# 0x2B.net
KiCad netlist of a schematic drawn in EasyEDA Pro
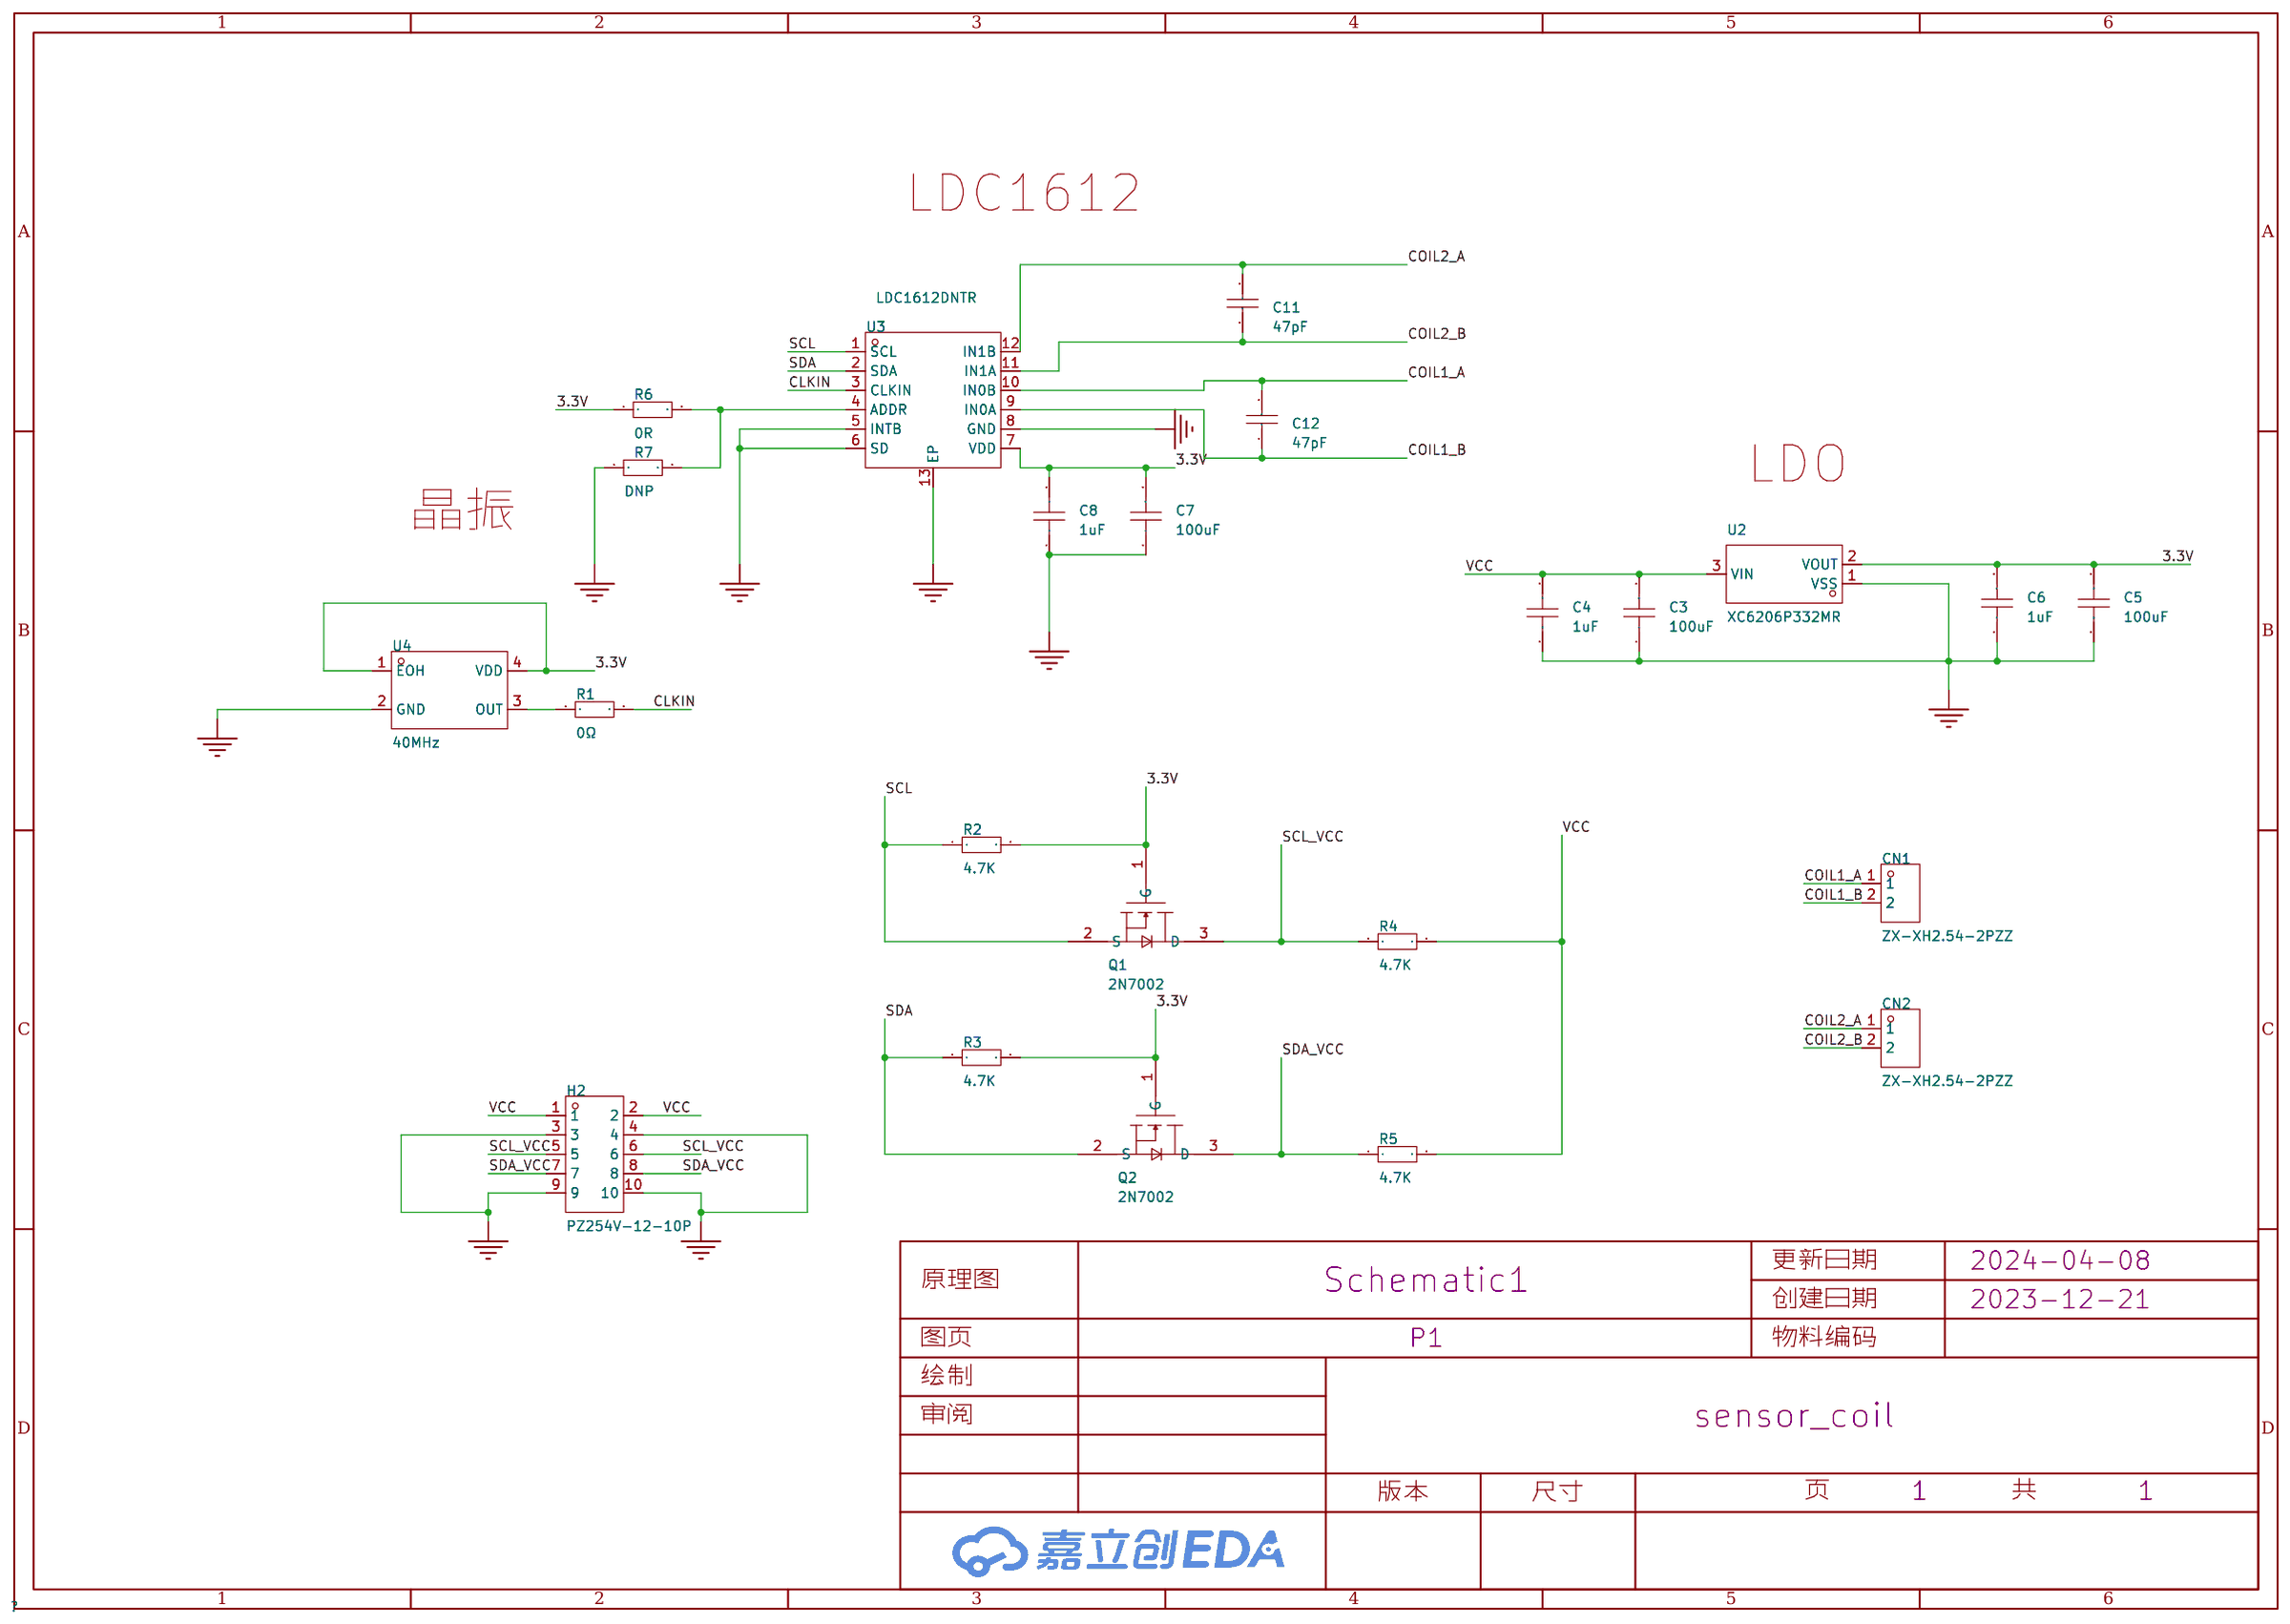
[diagram p0: schematic sheet]

(export (version "E")
  (design (tool "Eeschema 10.0.6"))
  (components
    (comp (ref "C3")
      (value "100uF")
      (footprint "easyedapro:C0603")
      (libsource (lib "easyedapro") (part "CapAcitance"))
    )
    (comp (ref "C4")
      (value "1uF")
      (footprint "easyedapro:C0603")
      (libsource (lib "easyedapro") (part "CapAcitance"))
    )
    (comp (ref "C5")
      (value "100uF")
      (footprint "easyedapro:C0603")
      (libsource (lib "easyedapro") (part "CapAcitance"))
    )
    (comp (ref "C6")
      (value "1uF")
      (footprint "easyedapro:C0603")
      (libsource (lib "easyedapro") (part "CapAcitance"))
    )
    (comp (ref "C7")
      (value "100uF")
      (footprint "easyedapro:C0603")
      (libsource (lib "easyedapro") (part "CapAcitance"))
    )
    (comp (ref "C8")
      (value "1uF")
      (footprint "easyedapro:C0603")
      (libsource (lib "easyedapro") (part "CapAcitance"))
    )
    (comp (ref "C11")
      (value "47pF")
      (footprint "easyedapro:C0402")
      (description "容值:47pF;精度:±5%;额定电压:50V;材质(温度系数):C0G;")
      (fields (field (name "Manufacturer Part") "0402CG470J500NT") (field (name "Manufacturer") "FH(风华)"))
      (libsource (lib "easyedapro") (part "0402CG470J500NT"))
    )
    (comp (ref "C12")
      (value "47pF")
      (footprint "easyedapro:C0402")
      (description "容值:47pF;精度:±5%;额定电压:50V;材质(温度系数):C0G;")
      (fields (field (name "Manufacturer Part") "0402CG470J500NT") (field (name "Manufacturer") "FH(风华)"))
      (libsource (lib "easyedapro") (part "0402CG470J500NT"))
    )
    (comp (ref "CN1")
      (value "ZX-XH2.54-2PZZ")
      (footprint "easyedapro:CONN-TH_2P-P2.50_HX25003-2A")
      (fields (field (name "Manufacturer") "Megastar(兆星)"))
      (libsource (lib "easyedapro") (part "ZX-XH2.54-2PZZ"))
    )
    (comp (ref "CN2")
      (value "ZX-XH2.54-2PZZ")
      (footprint "easyedapro:CONN-TH_2P-P2.50_HX25003-2A")
      (fields (field (name "Manufacturer") "Megastar(兆星)"))
      (libsource (lib "easyedapro") (part "ZX-XH2.54-2PZZ"))
    )
    (comp (ref "H2")
      (value "PZ254V-12-10P")
      (footprint "easyedapro:HDR-TH_10P-P2.54-V-M-R2-C5-S2.54")
      (fields (field (name "Manufacturer") "XFCN(兴飞)"))
      (libsource (lib "easyedapro") (part "PZ254V-12-10P"))
    )
    (comp (ref "Q1")
      (value "2N7002")
      (footprint "easyedapro:SOT-23-3_L2.9-W1.3-P1.90-LS2.4-BR")
      (fields (field (name "Manufacturer") "JSMSEMI(杰盛微)"))
      (libsource (lib "easyedapro") (part "2N7002_C916396"))
    )
    (comp (ref "Q2")
      (value "2N7002")
      (footprint "easyedapro:SOT-23-3_L2.9-W1.3-P1.90-LS2.4-BR")
      (fields (field (name "Manufacturer") "JSMSEMI(杰盛微)"))
      (libsource (lib "easyedapro") (part "2N7002_C916396"))
    )
    (comp (ref "R1") (value "0Ω") (footprint "easyedapro:R0603") (libsource (lib "easyedapro") (part "电阻")))
    (comp (ref "R2") (value "4.7K") (footprint "easyedapro:R0603") (libsource (lib "easyedapro") (part "电阻")))
    (comp (ref "R3") (value "4.7K") (footprint "easyedapro:R0603") (libsource (lib "easyedapro") (part "电阻")))
    (comp (ref "R4") (value "4.7K") (footprint "easyedapro:R0603") (libsource (lib "easyedapro") (part "电阻")))
    (comp (ref "R5") (value "4.7K") (footprint "easyedapro:R0603") (libsource (lib "easyedapro") (part "电阻")))
    (comp (ref "R6") (value "0R") (footprint "easyedapro:R0603") (libsource (lib "easyedapro") (part "电阻")))
    (comp (ref "R7") (value "DNP") (footprint "easyedapro:R0603") (libsource (lib "easyedapro") (part "电阻")))
    (comp (ref "U2")
      (value "XC6206P332MR")
      (footprint "easyedapro:SOT-23-3_L3.0-W1.7-P0.95-LS2.9-BR")
      (description "输出类型:固定;最大输入电压:8V;输出电压:3.3V;最大输出电流:250mA;电源纹波抑制比(PSRR):40dB@(1kHz);输出极性:正极;")
      (fields (field (name "Manufacturer") "UMW(友台半导体)"))
      (libsource (lib "easyedapro") (part "XC6206P332MR_C347376"))
    )
    (comp (ref "U3")
      (value "LDC1612DNTR")
      (footprint "easyedapro:WSON-12_L4.0-W4.0-P0.50-BL-EP")
      (description "LDC1612 2 通道、28 位、高分辨率电感数字转换器")
      (fields (field (name "Manufacturer") "TI(德州仪器)"))
      (libsource (lib "easyedapro") (part "LDC1612DNTR"))
    )
    (comp (ref "U4")
      (value "40MHz")
      (footprint "easyedapro:OSC-SMD_4P-L2.5-W2.0-BL")
      (description "频率:40MHz;输出模式:CMOS;工作电压:3.3V;供电电流:15mA;频率稳定度(全温):±50ppm;")
      (fields (field (name "Manufacturer Part") "625L3C040M00000") (field (name "Manufacturer") "CTS(西迪斯)"))
      (libsource (lib "easyedapro") (part "625L3C040M00000"))
    )
  )
  (nets
    (net (code "1") (name "/3.3V") (class "Default")
      (node (ref "C5") (pin "2") (pinfunction "2_2") (pintype "input"))
      (node (ref "C6") (pin "2") (pinfunction "2_2") (pintype "input"))
      (node (ref "C7") (pin "2") (pinfunction "2_2") (pintype "input"))
      (node (ref "C8") (pin "2") (pinfunction "2_2") (pintype "input"))
      (node (ref "Q1") (pin "1") (pinfunction "G_1") (pintype "unspecified"))
      (node (ref "Q2") (pin "1") (pinfunction "G_1") (pintype "unspecified"))
      (node (ref "R2") (pin "2") (pinfunction "2_2") (pintype "input"))
      (node (ref "R3") (pin "2") (pinfunction "2_2") (pintype "input"))
      (node (ref "R6") (pin "1") (pinfunction "1_1") (pintype "input"))
      (node (ref "U2") (pin "2") (pinfunction "VOUT_2") (pintype "unspecified"))
      (node (ref "U3") (pin "7") (pinfunction "VDD_7") (pintype "unspecified"))
      (node (ref "U4") (pin "1") (pinfunction "EOH_1") (pintype "unspecified"))
      (node (ref "U4") (pin "4") (pinfunction "VDD_4") (pintype "unspecified"))
    )
    (net (code "2") (name "/CLKIN") (class "Default")
      (node (ref "R1") (pin "2") (pinfunction "2_2") (pintype "input"))
      (node (ref "U3") (pin "3") (pinfunction "CLKIN_3") (pintype "unspecified"))
    )
    (net (code "3") (name "/COIL1_A") (class "Default")
      (node (ref "C12") (pin "2") (pinfunction "2_2") (pintype "input"))
      (node (ref "CN1") (pin "1") (pinfunction "1_1") (pintype "unspecified"))
      (node (ref "U3") (pin "10") (pinfunction "IN0B_10") (pintype "unspecified"))
    )
    (net (code "4") (name "/COIL1_B") (class "Default")
      (node (ref "C12") (pin "1") (pinfunction "1_1") (pintype "input"))
      (node (ref "CN1") (pin "2") (pinfunction "2_2") (pintype "unspecified"))
      (node (ref "U3") (pin "9") (pinfunction "IN0A_9") (pintype "unspecified"))
    )
    (net (code "5") (name "/COIL2_A") (class "Default")
      (node (ref "C11") (pin "2") (pinfunction "2_2") (pintype "input"))
      (node (ref "CN2") (pin "1") (pinfunction "1_1") (pintype "unspecified"))
      (node (ref "U3") (pin "12") (pinfunction "IN1B_12") (pintype "unspecified"))
    )
    (net (code "6") (name "/COIL2_B") (class "Default")
      (node (ref "C11") (pin "1") (pinfunction "1_1") (pintype "input"))
      (node (ref "CN2") (pin "2") (pinfunction "2_2") (pintype "unspecified"))
      (node (ref "U3") (pin "11") (pinfunction "IN1A_11") (pintype "unspecified"))
    )
    (net (code "7") (name "/SCL") (class "Default")
      (node (ref "Q1") (pin "2") (pinfunction "S_2") (pintype "unspecified"))
      (node (ref "R2") (pin "1") (pinfunction "1_1") (pintype "input"))
      (node (ref "U3") (pin "1") (pinfunction "SCL_1") (pintype "unspecified"))
    )
    (net (code "8") (name "/SCL_VCC") (class "Default")
      (node (ref "H2") (pin "5") (pinfunction "5_5") (pintype "unspecified"))
      (node (ref "H2") (pin "6") (pinfunction "6_6") (pintype "unspecified"))
      (node (ref "Q1") (pin "3") (pinfunction "D_3") (pintype "unspecified"))
      (node (ref "R4") (pin "1") (pinfunction "1_1") (pintype "input"))
    )
    (net (code "9") (name "/SDA") (class "Default")
      (node (ref "Q2") (pin "2") (pinfunction "S_2") (pintype "unspecified"))
      (node (ref "R3") (pin "1") (pinfunction "1_1") (pintype "input"))
      (node (ref "U3") (pin "2") (pinfunction "SDA_2") (pintype "unspecified"))
    )
    (net (code "10") (name "/SDA_VCC") (class "Default")
      (node (ref "H2") (pin "7") (pinfunction "7_7") (pintype "unspecified"))
      (node (ref "H2") (pin "8") (pinfunction "8_8") (pintype "unspecified"))
      (node (ref "Q2") (pin "3") (pinfunction "D_3") (pintype "unspecified"))
      (node (ref "R5") (pin "1") (pinfunction "1_1") (pintype "input"))
    )
    (net (code "11") (name "/VCC") (class "Default")
      (node (ref "C3") (pin "2") (pinfunction "2_2") (pintype "input"))
      (node (ref "C4") (pin "2") (pinfunction "2_2") (pintype "input"))
      (node (ref "H2") (pin "1") (pinfunction "1_1") (pintype "unspecified"))
      (node (ref "H2") (pin "2") (pinfunction "2_2") (pintype "unspecified"))
      (node (ref "R4") (pin "2") (pinfunction "2_2") (pintype "input"))
      (node (ref "R5") (pin "2") (pinfunction "2_2") (pintype "input"))
      (node (ref "U2") (pin "3") (pinfunction "VIN_3") (pintype "unspecified"))
    )
    (net (code "12") (name "GND") (class "Default")
      (node (ref "C3") (pin "1") (pinfunction "1_1") (pintype "input"))
      (node (ref "C4") (pin "1") (pinfunction "1_1") (pintype "input"))
      (node (ref "C5") (pin "1") (pinfunction "1_1") (pintype "input"))
      (node (ref "C6") (pin "1") (pinfunction "1_1") (pintype "input"))
      (node (ref "C7") (pin "1") (pinfunction "1_1") (pintype "input"))
      (node (ref "C8") (pin "1") (pinfunction "1_1") (pintype "input"))
      (node (ref "H2") (pin "10") (pinfunction "10_10") (pintype "unspecified"))
      (node (ref "H2") (pin "3") (pinfunction "3_3") (pintype "unspecified"))
      (node (ref "H2") (pin "4") (pinfunction "4_4") (pintype "unspecified"))
      (node (ref "H2") (pin "9") (pinfunction "9_9") (pintype "unspecified"))
      (node (ref "R7") (pin "1") (pinfunction "1_1") (pintype "input"))
      (node (ref "U2") (pin "1") (pinfunction "VSS_1") (pintype "unspecified"))
      (node (ref "U3") (pin "13") (pinfunction "EP_13") (pintype "unspecified"))
      (node (ref "U3") (pin "5") (pinfunction "INTB_5") (pintype "unspecified"))
      (node (ref "U3") (pin "6") (pinfunction "SD_6") (pintype "unspecified"))
      (node (ref "U3") (pin "8") (pinfunction "GND_8") (pintype "unspecified"))
      (node (ref "U4") (pin "2") (pinfunction "GND_2") (pintype "unspecified"))
    )
    (net (code "13") (name "Net-(U3-ADDR)") (class "Default")
      (node (ref "R6") (pin "2") (pinfunction "2_2") (pintype "input"))
      (node (ref "R7") (pin "2") (pinfunction "2_2") (pintype "input"))
      (node (ref "U3") (pin "4") (pinfunction "ADDR_4") (pintype "unspecified"))
    )
    (net (code "14") (name "Net-(U4-OUT)") (class "Default")
      (node (ref "R1") (pin "1") (pinfunction "1_1") (pintype "input"))
      (node (ref "U4") (pin "3") (pinfunction "OUT_3") (pintype "unspecified"))
    )
  )
)
